# 1_Power.net
KiCad netlist of a schematic drawn in Altium Designer
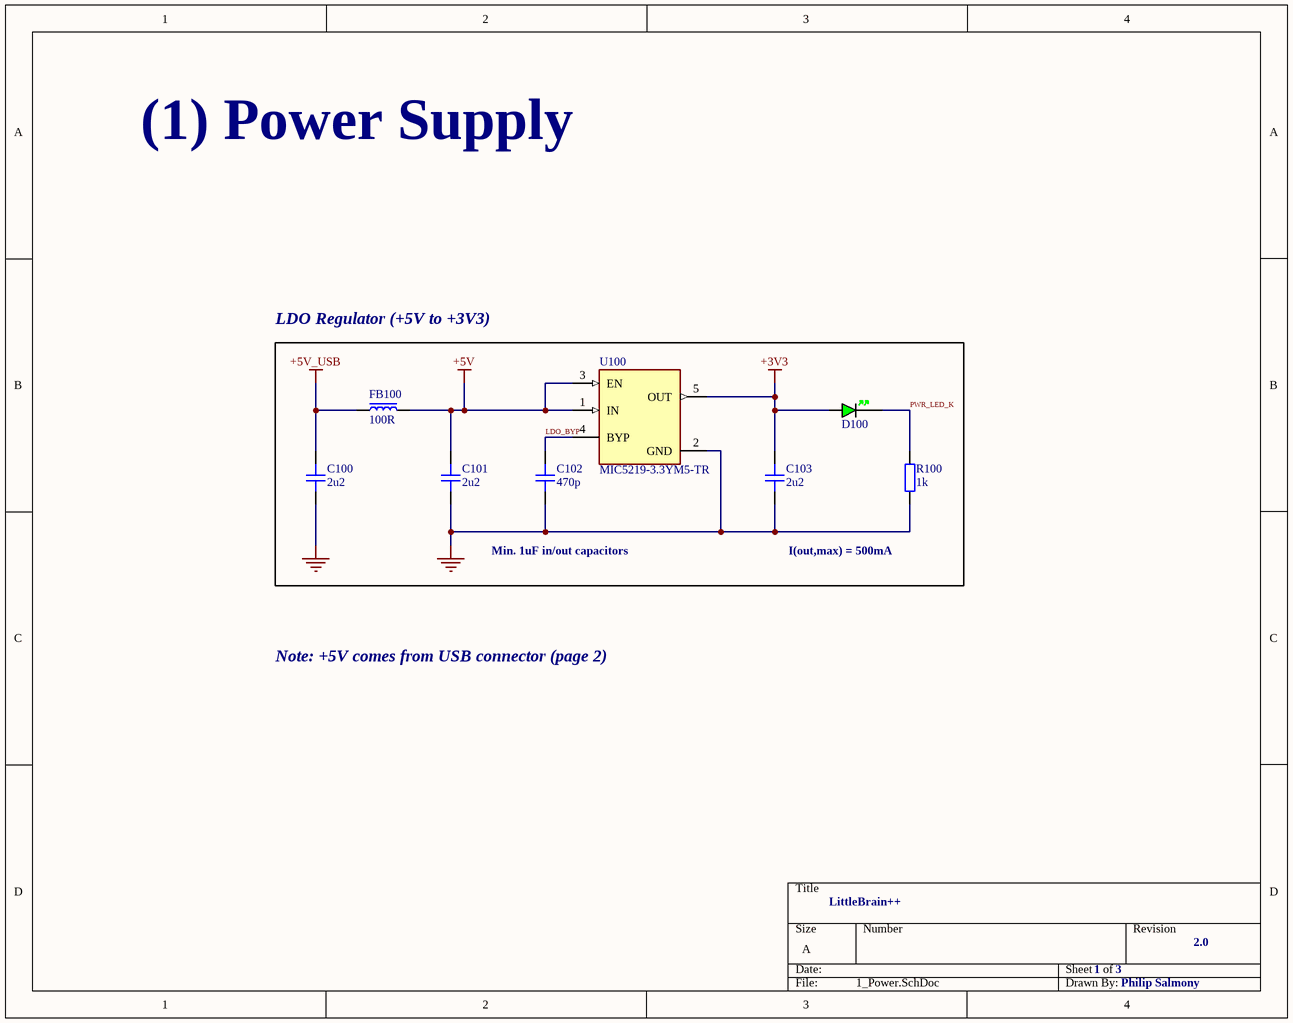
[diagram p0: 1_Power.SchDoc]

(export (version "E")
  (design (tool "Eeschema 10.0.6"))
  (components
    (comp (ref "C100")
      (value "2u2")
      (footprint "CAP_0603")
      (description "Capacitor SMD 0603 16V")
      (libsource (lib "Schematic-Lib-PhilsLab") (part "CAP_0603_16V"))
    )
    (comp (ref "C101")
      (value "2u2")
      (footprint "CAP_0603")
      (description "Capacitor SMD 0603 16V")
      (libsource (lib "Schematic-Lib-PhilsLab") (part "CAP_0603_16V"))
    )
    (comp (ref "C102")
      (value "470p")
      (footprint "CAP_0402")
      (description "Capacitor SMD 0402 16V")
      (libsource (lib "Schematic-Lib-PhilsLab") (part "CAP_0402_16V"))
    )
    (comp (ref "C103")
      (value "2u2")
      (footprint "CAP_0603")
      (description "Capacitor SMD 0603 16V")
      (libsource (lib "Schematic-Lib-PhilsLab") (part "CAP_0603_16V"))
    )
    (comp (ref "D100")
      (value "GREEN")
      (footprint "LED_0402_GREEN")
      (description "LED 0402 GREEN SMD")
      (libsource (lib "Schematic-Lib-PhilsLab") (part "LED_0402_GREEN"))
    )
    (comp (ref "FB100")
      (value "100R")
      (footprint "FB_0603")
      (description "Ferrite Bead SMD 0603")
      (libsource (lib "Schematic-Lib-PhilsLab") (part "FB_0603"))
    )
    (comp (ref "R100")
      (value "1k")
      (footprint "RES_0402")
      (description "Resistor SMD 0402")
      (libsource (lib "Schematic-Lib-PhilsLab") (part "RES_0402"))
    )
    (comp (ref "U100")
      (value "MIC5219-3.3YM5-TR")
      (footprint "FP-SOT23-5LD-PL-1-IPC_A")
      (description "IC REG LINEAR 3.3V 500MA SOT23-5")
      (libsource (lib "Altium Content Vault") (part "16b36b16d6b7b40c29ab14718bc3058"))
    )
  )
  (nets
    (net (code "1") (name "+3V3") (class "Default")
      (node (ref "C103") (pin "2") (pinfunction "2_2") (pintype "passive"))
      (node (ref "D100") (pin "A") (pinfunction "A_A") (pintype "passive"))
      (node (ref "U100") (pin "5") (pinfunction "OUT_5") (pintype "output"))
    )
    (net (code "2") (name "+5V") (class "Default")
      (node (ref "C101") (pin "2") (pinfunction "2_2") (pintype "passive"))
      (node (ref "FB100") (pin "2") (pinfunction "2_2") (pintype "passive"))
      (node (ref "U100") (pin "1") (pinfunction "IN_1") (pintype "input"))
      (node (ref "U100") (pin "3") (pinfunction "EN_3") (pintype "input"))
    )
    (net (code "3") (name "+5V_USB") (class "Default")
      (node (ref "C100") (pin "2") (pinfunction "2_2") (pintype "passive"))
      (node (ref "FB100") (pin "1") (pinfunction "1_1") (pintype "passive"))
    )
    (net (code "4") (name "/LDO_BYP") (class "Default")
      (node (ref "C102") (pin "2") (pinfunction "2_2") (pintype "passive"))
      (node (ref "U100") (pin "4") (pinfunction "BYP_4") (pintype "passive"))
    )
    (net (code "5") (name "/PWR_LED_K") (class "Default")
      (node (ref "D100") (pin "K") (pinfunction "K_K") (pintype "passive"))
      (node (ref "R100") (pin "2") (pinfunction "2_2") (pintype "passive"))
    )
    (net (code "6") (name "GND") (class "Default")
      (node (ref "C100") (pin "1") (pinfunction "1_1") (pintype "passive"))
      (node (ref "C101") (pin "1") (pinfunction "1_1") (pintype "passive"))
      (node (ref "C102") (pin "1") (pinfunction "1_1") (pintype "passive"))
      (node (ref "C103") (pin "1") (pinfunction "1_1") (pintype "passive"))
      (node (ref "R100") (pin "1") (pinfunction "1_1") (pintype "passive"))
      (node (ref "U100") (pin "2") (pinfunction "GND_2") (pintype "power_in"))
    )
  )
)
